# cover.net
KiCad netlist of a schematic drawn in Altium Designer
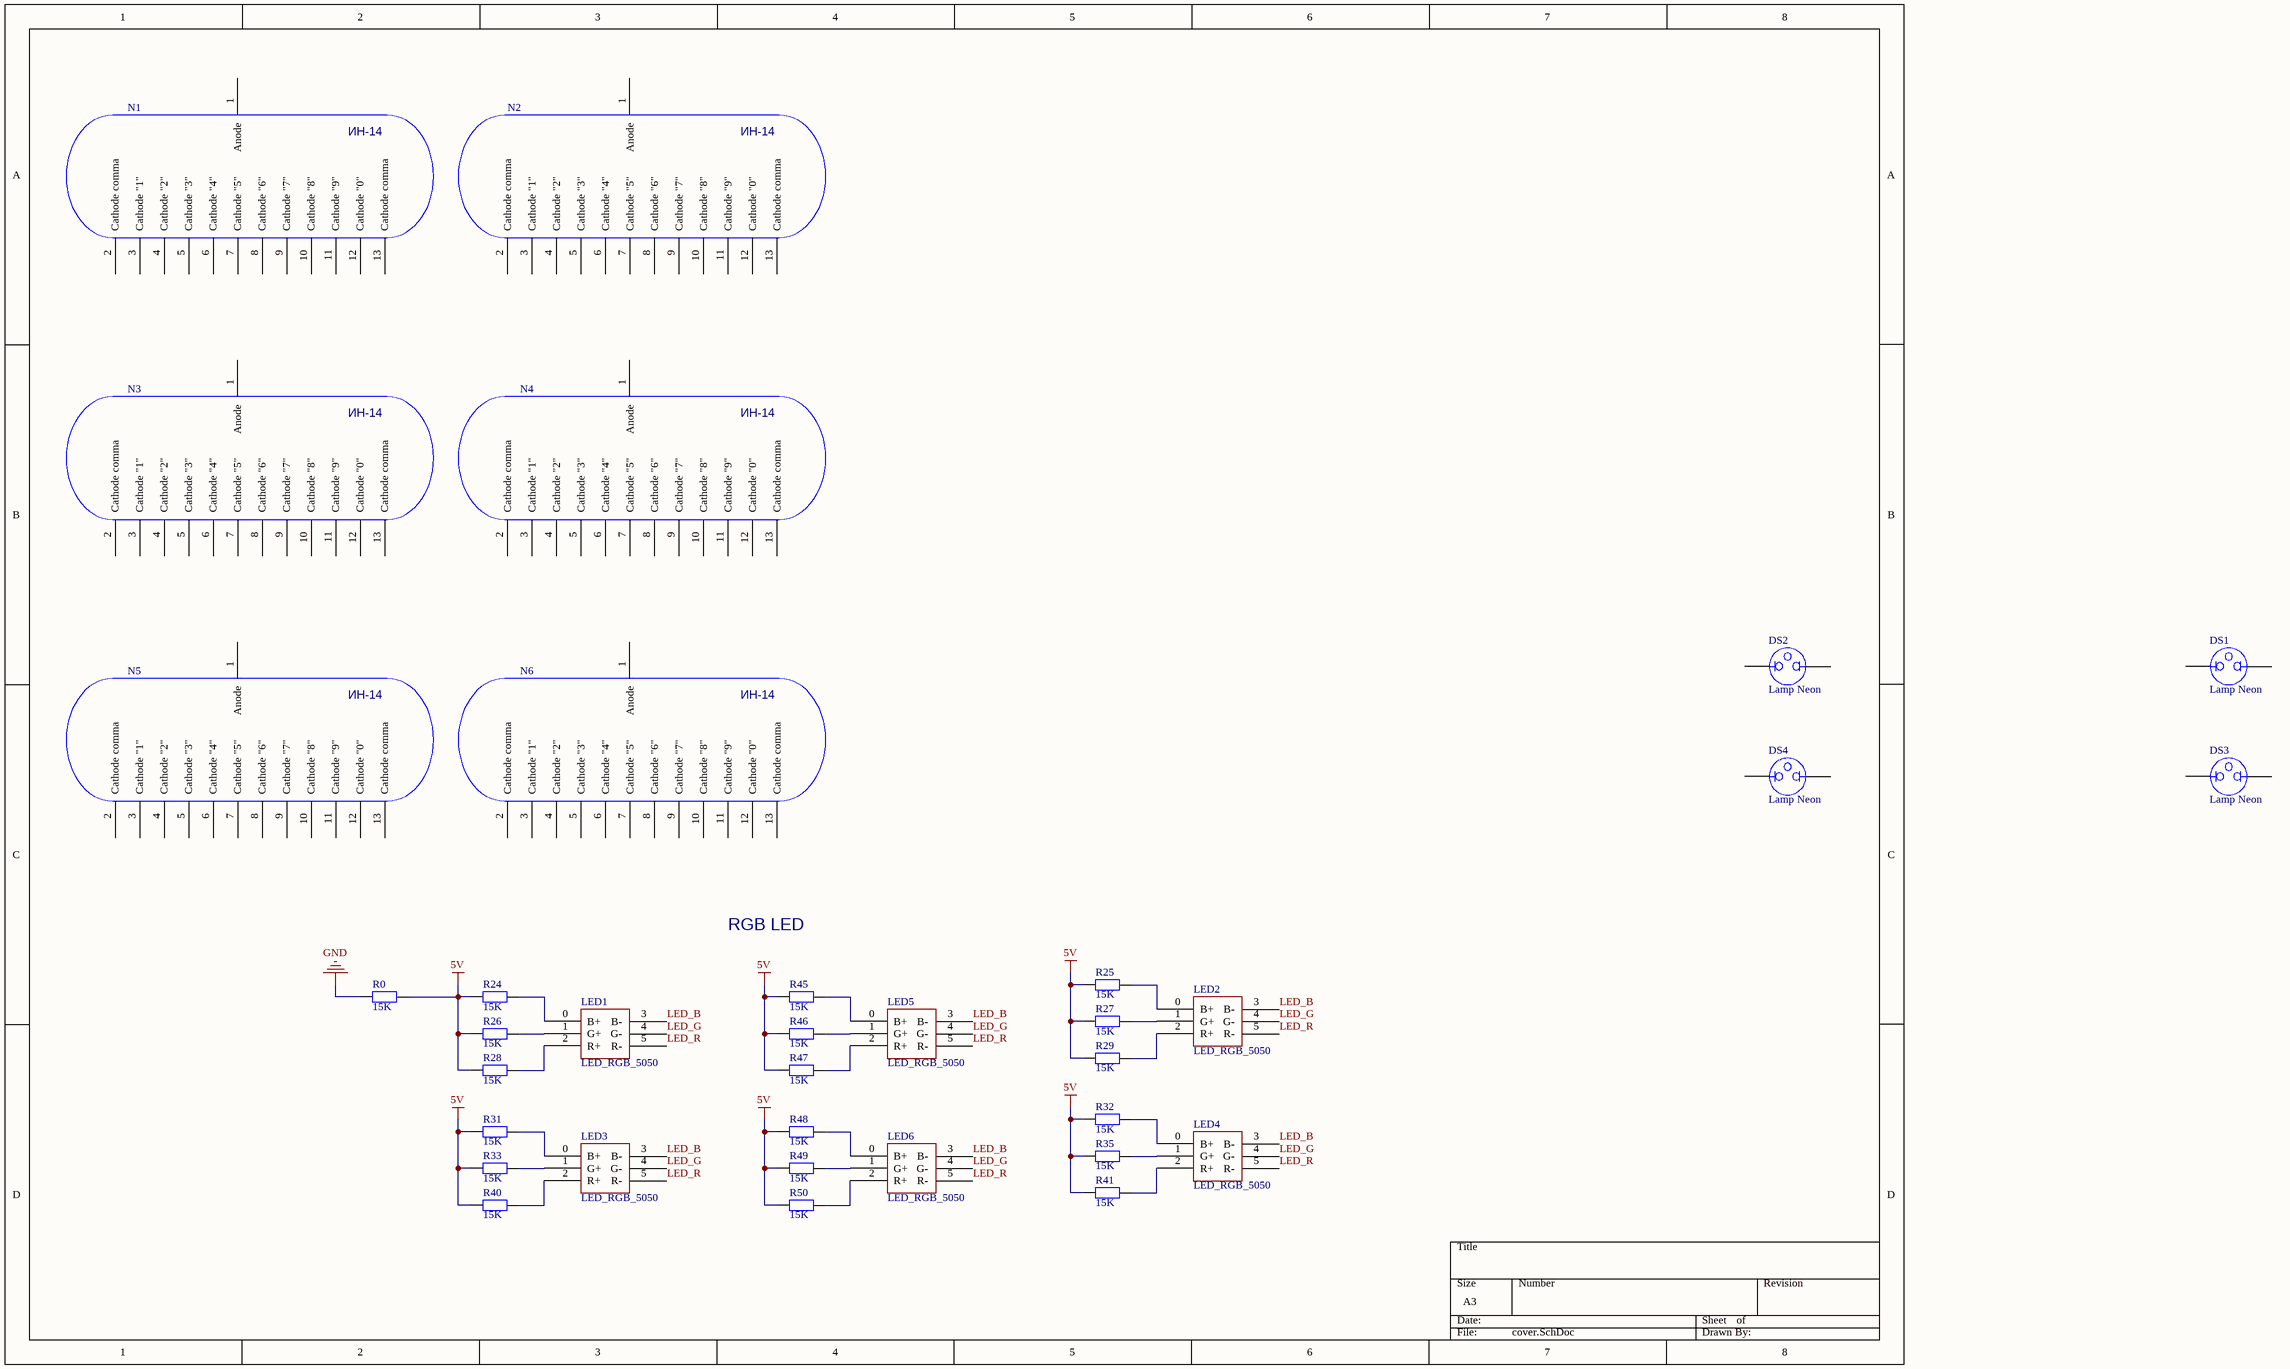
[diagram p0: cover.SchDoc]

(export (version "E")
  (design (tool "Eeschema 10.0.6"))
  (components
    (comp (ref "DS1")
      (value "Lamp Neon")
      (footprint "LED_PIN2")
      (description "Neon Lamp")
      (fields (field (name "PUBLISHER") "Altium Limited"))
      (libsource (lib "Miscellaneous Devices") (part "Lamp Neon"))
    )
    (comp (ref "DS2")
      (value "Lamp Neon")
      (footprint "LED_PIN2")
      (description "Neon Lamp")
      (fields (field (name "PUBLISHER") "Altium Limited"))
      (libsource (lib "Miscellaneous Devices") (part "Lamp Neon"))
    )
    (comp (ref "DS3")
      (value "Lamp Neon")
      (footprint "LED_PIN2")
      (description "Neon Lamp")
      (fields (field (name "PUBLISHER") "Altium Limited"))
      (libsource (lib "Miscellaneous Devices") (part "Lamp Neon"))
    )
    (comp (ref "DS4")
      (value "Lamp Neon")
      (footprint "LED_PIN2")
      (description "Neon Lamp")
      (fields (field (name "PUBLISHER") "Altium Limited"))
      (libsource (lib "Miscellaneous Devices") (part "Lamp Neon"))
    )
    (comp (ref "LED1")
      (value "LED_RGB_5050")
      (footprint "LED_RGB_5050")
      (libsource (lib "SCH") (part "LED_RGB_5050"))
    )
    (comp (ref "LED2")
      (value "LED_RGB_5050")
      (footprint "LED_RGB_5050")
      (libsource (lib "SCH") (part "LED_RGB_5050"))
    )
    (comp (ref "LED3")
      (value "LED_RGB_5050")
      (footprint "LED_RGB_5050")
      (libsource (lib "SCH") (part "LED_RGB_5050"))
    )
    (comp (ref "LED4")
      (value "LED_RGB_5050")
      (footprint "LED_RGB_5050")
      (libsource (lib "SCH") (part "LED_RGB_5050"))
    )
    (comp (ref "LED5")
      (value "LED_RGB_5050")
      (footprint "LED_RGB_5050")
      (libsource (lib "SCH") (part "LED_RGB_5050"))
    )
    (comp (ref "LED6")
      (value "LED_RGB_5050")
      (footprint "LED_RGB_5050")
      (libsource (lib "SCH") (part "LED_RGB_5050"))
    )
    (comp (ref "N1") (value "ИН-14") (footprint "IN14") (libsource (lib "NIXIEClock_SCHLib") (part "ИН-14")))
    (comp (ref "N2") (value "ИН-14") (footprint "IN14") (libsource (lib "NIXIEClock_SCHLib") (part "ИН-14")))
    (comp (ref "N3") (value "ИН-14") (footprint "IN14") (libsource (lib "NIXIEClock_SCHLib") (part "ИН-14")))
    (comp (ref "N4") (value "ИН-14") (footprint "IN14") (libsource (lib "NIXIEClock_SCHLib") (part "ИН-14")))
    (comp (ref "N5") (value "ИН-14") (footprint "IN14") (libsource (lib "NIXIEClock_SCHLib") (part "ИН-14")))
    (comp (ref "N6") (value "ИН-14") (footprint "IN14") (libsource (lib "NIXIEClock_SCHLib") (part "ИН-14")))
    (comp (ref "R0")
      (value "15K")
      (footprint "R 0603")
      (description "Resistor")
      (fields (field (name "Comment") "Res2") (field (name "PUBLISHER") "Altium Limited"))
      (libsource (lib "Miscellaneous Devices") (part "Res2"))
    )
    (comp (ref "R24")
      (value "15K")
      (footprint "R 0603")
      (description "Resistor")
      (fields (field (name "Comment") "Res2") (field (name "PUBLISHER") "Altium Limited"))
      (libsource (lib "Miscellaneous Devices") (part "Res2"))
    )
    (comp (ref "R25")
      (value "15K")
      (footprint "R 0603")
      (description "Resistor")
      (fields (field (name "Comment") "Res2") (field (name "PUBLISHER") "Altium Limited"))
      (libsource (lib "Miscellaneous Devices") (part "Res2"))
    )
    (comp (ref "R26")
      (value "15K")
      (footprint "R 0603")
      (description "Resistor")
      (fields (field (name "Comment") "Res2") (field (name "PUBLISHER") "Altium Limited"))
      (libsource (lib "Miscellaneous Devices") (part "Res2"))
    )
    (comp (ref "R27")
      (value "15K")
      (footprint "R 0603")
      (description "Resistor")
      (fields (field (name "Comment") "Res2") (field (name "PUBLISHER") "Altium Limited"))
      (libsource (lib "Miscellaneous Devices") (part "Res2"))
    )
    (comp (ref "R28")
      (value "15K")
      (footprint "R 0603")
      (description "Resistor")
      (fields (field (name "Comment") "Res2") (field (name "PUBLISHER") "Altium Limited"))
      (libsource (lib "Miscellaneous Devices") (part "Res2"))
    )
    (comp (ref "R29")
      (value "15K")
      (footprint "R 0603")
      (description "Resistor")
      (fields (field (name "Comment") "Res2") (field (name "PUBLISHER") "Altium Limited"))
      (libsource (lib "Miscellaneous Devices") (part "Res2"))
    )
    (comp (ref "R31")
      (value "15K")
      (footprint "R 0603")
      (description "Resistor")
      (fields (field (name "Comment") "Res2") (field (name "PUBLISHER") "Altium Limited"))
      (libsource (lib "Miscellaneous Devices") (part "Res2"))
    )
    (comp (ref "R32")
      (value "15K")
      (footprint "R 0603")
      (description "Resistor")
      (fields (field (name "Comment") "Res2") (field (name "PUBLISHER") "Altium Limited"))
      (libsource (lib "Miscellaneous Devices") (part "Res2"))
    )
    (comp (ref "R33")
      (value "15K")
      (footprint "R 0603")
      (description "Resistor")
      (fields (field (name "Comment") "Res2") (field (name "PUBLISHER") "Altium Limited"))
      (libsource (lib "Miscellaneous Devices") (part "Res2"))
    )
    (comp (ref "R35")
      (value "15K")
      (footprint "R 0603")
      (description "Resistor")
      (fields (field (name "Comment") "Res2") (field (name "PUBLISHER") "Altium Limited"))
      (libsource (lib "Miscellaneous Devices") (part "Res2"))
    )
    (comp (ref "R40")
      (value "15K")
      (footprint "R 0603")
      (description "Resistor")
      (fields (field (name "Comment") "Res2") (field (name "PUBLISHER") "Altium Limited"))
      (libsource (lib "Miscellaneous Devices") (part "Res2"))
    )
    (comp (ref "R41")
      (value "15K")
      (footprint "R 0603")
      (description "Resistor")
      (fields (field (name "Comment") "Res2") (field (name "PUBLISHER") "Altium Limited"))
      (libsource (lib "Miscellaneous Devices") (part "Res2"))
    )
    (comp (ref "R45")
      (value "15K")
      (footprint "R 0603")
      (description "Resistor")
      (fields (field (name "Comment") "Res2") (field (name "PUBLISHER") "Altium Limited"))
      (libsource (lib "Miscellaneous Devices") (part "Res2"))
    )
    (comp (ref "R46")
      (value "15K")
      (footprint "R 0603")
      (description "Resistor")
      (fields (field (name "Comment") "Res2") (field (name "PUBLISHER") "Altium Limited"))
      (libsource (lib "Miscellaneous Devices") (part "Res2"))
    )
    (comp (ref "R47")
      (value "15K")
      (footprint "R 0603")
      (description "Resistor")
      (fields (field (name "Comment") "Res2") (field (name "PUBLISHER") "Altium Limited"))
      (libsource (lib "Miscellaneous Devices") (part "Res2"))
    )
    (comp (ref "R48")
      (value "15K")
      (footprint "R 0603")
      (description "Resistor")
      (fields (field (name "Comment") "Res2") (field (name "PUBLISHER") "Altium Limited"))
      (libsource (lib "Miscellaneous Devices") (part "Res2"))
    )
    (comp (ref "R49")
      (value "15K")
      (footprint "R 0603")
      (description "Resistor")
      (fields (field (name "Comment") "Res2") (field (name "PUBLISHER") "Altium Limited"))
      (libsource (lib "Miscellaneous Devices") (part "Res2"))
    )
    (comp (ref "R50")
      (value "15K")
      (footprint "R 0603")
      (description "Resistor")
      (fields (field (name "Comment") "Res2") (field (name "PUBLISHER") "Altium Limited"))
      (libsource (lib "Miscellaneous Devices") (part "Res2"))
    )
  )
  (nets
    (net (code "1") (name "/LED_B") (class "Default")
      (node (ref "LED1") (pin "3") (pinfunction "B-_3") (pintype "passive"))
      (node (ref "LED2") (pin "3") (pinfunction "B-_3") (pintype "passive"))
      (node (ref "LED3") (pin "3") (pinfunction "B-_3") (pintype "passive"))
      (node (ref "LED4") (pin "3") (pinfunction "B-_3") (pintype "passive"))
      (node (ref "LED5") (pin "3") (pinfunction "B-_3") (pintype "passive"))
      (node (ref "LED6") (pin "3") (pinfunction "B-_3") (pintype "passive"))
    )
    (net (code "2") (name "/LED_G") (class "Default")
      (node (ref "LED1") (pin "4") (pinfunction "G-_4") (pintype "passive"))
      (node (ref "LED2") (pin "4") (pinfunction "G-_4") (pintype "passive"))
      (node (ref "LED3") (pin "4") (pinfunction "G-_4") (pintype "passive"))
      (node (ref "LED4") (pin "4") (pinfunction "G-_4") (pintype "passive"))
      (node (ref "LED5") (pin "4") (pinfunction "G-_4") (pintype "passive"))
      (node (ref "LED6") (pin "4") (pinfunction "G-_4") (pintype "passive"))
    )
    (net (code "3") (name "/LED_R") (class "Default")
      (node (ref "LED1") (pin "5") (pinfunction "R-_5") (pintype "passive"))
      (node (ref "LED2") (pin "5") (pinfunction "R-_5") (pintype "passive"))
      (node (ref "LED3") (pin "5") (pinfunction "R-_5") (pintype "passive"))
      (node (ref "LED4") (pin "5") (pinfunction "R-_5") (pintype "passive"))
      (node (ref "LED5") (pin "5") (pinfunction "R-_5") (pintype "passive"))
      (node (ref "LED6") (pin "5") (pinfunction "R-_5") (pintype "passive"))
    )
    (net (code "4") (name "5V") (class "Default")
      (node (ref "R0") (pin "1") (pinfunction "1_1") (pintype "passive"))
      (node (ref "R24") (pin "2") (pinfunction "2_2") (pintype "passive"))
      (node (ref "R25") (pin "2") (pinfunction "2_2") (pintype "passive"))
      (node (ref "R26") (pin "2") (pinfunction "2_2") (pintype "passive"))
      (node (ref "R27") (pin "2") (pinfunction "2_2") (pintype "passive"))
      (node (ref "R28") (pin "2") (pinfunction "2_2") (pintype "passive"))
      (node (ref "R29") (pin "2") (pinfunction "2_2") (pintype "passive"))
      (node (ref "R31") (pin "2") (pinfunction "2_2") (pintype "passive"))
      (node (ref "R32") (pin "2") (pinfunction "2_2") (pintype "passive"))
      (node (ref "R33") (pin "2") (pinfunction "2_2") (pintype "passive"))
      (node (ref "R35") (pin "2") (pinfunction "2_2") (pintype "passive"))
      (node (ref "R40") (pin "2") (pinfunction "2_2") (pintype "passive"))
      (node (ref "R41") (pin "2") (pinfunction "2_2") (pintype "passive"))
      (node (ref "R45") (pin "2") (pinfunction "2_2") (pintype "passive"))
      (node (ref "R46") (pin "2") (pinfunction "2_2") (pintype "passive"))
      (node (ref "R47") (pin "2") (pinfunction "2_2") (pintype "passive"))
      (node (ref "R48") (pin "2") (pinfunction "2_2") (pintype "passive"))
      (node (ref "R49") (pin "2") (pinfunction "2_2") (pintype "passive"))
      (node (ref "R50") (pin "2") (pinfunction "2_2") (pintype "passive"))
    )
    (net (code "5") (name "GND") (class "Default")
      (node (ref "R0") (pin "2") (pinfunction "2_2") (pintype "passive"))
    )
    (net (code "6") (name "Net-(LED1-B+)") (class "Default")
      (node (ref "LED1") (pin "0") (pinfunction "B+_0") (pintype "passive"))
      (node (ref "R24") (pin "1") (pinfunction "1_1") (pintype "passive"))
    )
    (net (code "7") (name "Net-(LED1-G+)") (class "Default")
      (node (ref "LED1") (pin "1") (pinfunction "G+_1") (pintype "passive"))
      (node (ref "R26") (pin "1") (pinfunction "1_1") (pintype "passive"))
    )
    (net (code "8") (name "Net-(LED1-R+)") (class "Default")
      (node (ref "LED1") (pin "2") (pinfunction "R+_2") (pintype "passive"))
      (node (ref "R28") (pin "1") (pinfunction "1_1") (pintype "passive"))
    )
    (net (code "9") (name "Net-(LED2-B+)") (class "Default")
      (node (ref "LED2") (pin "0") (pinfunction "B+_0") (pintype "passive"))
      (node (ref "R25") (pin "1") (pinfunction "1_1") (pintype "passive"))
    )
    (net (code "10") (name "Net-(LED2-G+)") (class "Default")
      (node (ref "LED2") (pin "1") (pinfunction "G+_1") (pintype "passive"))
      (node (ref "R27") (pin "1") (pinfunction "1_1") (pintype "passive"))
    )
    (net (code "11") (name "Net-(LED2-R+)") (class "Default")
      (node (ref "LED2") (pin "2") (pinfunction "R+_2") (pintype "passive"))
      (node (ref "R29") (pin "1") (pinfunction "1_1") (pintype "passive"))
    )
    (net (code "12") (name "Net-(LED3-B+)") (class "Default")
      (node (ref "LED3") (pin "0") (pinfunction "B+_0") (pintype "passive"))
      (node (ref "R31") (pin "1") (pinfunction "1_1") (pintype "passive"))
    )
    (net (code "13") (name "Net-(LED3-G+)") (class "Default")
      (node (ref "LED3") (pin "1") (pinfunction "G+_1") (pintype "passive"))
      (node (ref "R33") (pin "1") (pinfunction "1_1") (pintype "passive"))
    )
    (net (code "14") (name "Net-(LED3-R+)") (class "Default")
      (node (ref "LED3") (pin "2") (pinfunction "R+_2") (pintype "passive"))
      (node (ref "R40") (pin "1") (pinfunction "1_1") (pintype "passive"))
    )
    (net (code "15") (name "Net-(LED4-B+)") (class "Default")
      (node (ref "LED4") (pin "0") (pinfunction "B+_0") (pintype "passive"))
      (node (ref "R32") (pin "1") (pinfunction "1_1") (pintype "passive"))
    )
    (net (code "16") (name "Net-(LED4-G+)") (class "Default")
      (node (ref "LED4") (pin "1") (pinfunction "G+_1") (pintype "passive"))
      (node (ref "R35") (pin "1") (pinfunction "1_1") (pintype "passive"))
    )
    (net (code "17") (name "Net-(LED4-R+)") (class "Default")
      (node (ref "LED4") (pin "2") (pinfunction "R+_2") (pintype "passive"))
      (node (ref "R41") (pin "1") (pinfunction "1_1") (pintype "passive"))
    )
    (net (code "18") (name "Net-(LED5-B+)") (class "Default")
      (node (ref "LED5") (pin "0") (pinfunction "B+_0") (pintype "passive"))
      (node (ref "R45") (pin "1") (pinfunction "1_1") (pintype "passive"))
    )
    (net (code "19") (name "Net-(LED5-G+)") (class "Default")
      (node (ref "LED5") (pin "1") (pinfunction "G+_1") (pintype "passive"))
      (node (ref "R46") (pin "1") (pinfunction "1_1") (pintype "passive"))
    )
    (net (code "20") (name "Net-(LED5-R+)") (class "Default")
      (node (ref "LED5") (pin "2") (pinfunction "R+_2") (pintype "passive"))
      (node (ref "R47") (pin "1") (pinfunction "1_1") (pintype "passive"))
    )
    (net (code "21") (name "Net-(LED6-B+)") (class "Default")
      (node (ref "LED6") (pin "0") (pinfunction "B+_0") (pintype "passive"))
      (node (ref "R48") (pin "1") (pinfunction "1_1") (pintype "passive"))
    )
    (net (code "22") (name "Net-(LED6-G+)") (class "Default")
      (node (ref "LED6") (pin "1") (pinfunction "G+_1") (pintype "passive"))
      (node (ref "R49") (pin "1") (pinfunction "1_1") (pintype "passive"))
    )
    (net (code "23") (name "Net-(LED6-R+)") (class "Default")
      (node (ref "LED6") (pin "2") (pinfunction "R+_2") (pintype "passive"))
      (node (ref "R50") (pin "1") (pinfunction "1_1") (pintype "passive"))
    )
    (net (code "24") (name "unconnected-(DS1-Pad1)") (class "Default")
      (node (ref "DS1") (pin "1") (pinfunction "1_1") (pintype "passive"))
    )
    (net (code "25") (name "unconnected-(DS1-Pad2)") (class "Default")
      (node (ref "DS1") (pin "2") (pinfunction "2_2") (pintype "passive"))
    )
    (net (code "26") (name "unconnected-(DS2-Pad1)") (class "Default")
      (node (ref "DS2") (pin "1") (pinfunction "1_1") (pintype "passive"))
    )
    (net (code "27") (name "unconnected-(DS2-Pad2)") (class "Default")
      (node (ref "DS2") (pin "2") (pinfunction "2_2") (pintype "passive"))
    )
    (net (code "28") (name "unconnected-(DS3-Pad1)") (class "Default")
      (node (ref "DS3") (pin "1") (pinfunction "1_1") (pintype "passive"))
    )
    (net (code "29") (name "unconnected-(DS3-Pad2)") (class "Default")
      (node (ref "DS3") (pin "2") (pinfunction "2_2") (pintype "passive"))
    )
    (net (code "30") (name "unconnected-(DS4-Pad1)") (class "Default")
      (node (ref "DS4") (pin "1") (pinfunction "1_1") (pintype "passive"))
    )
    (net (code "31") (name "unconnected-(DS4-Pad2)") (class "Default")
      (node (ref "DS4") (pin "2") (pinfunction "2_2") (pintype "passive"))
    )
    (net (code "32") (name "unconnected-(N1-Anode-Pad1)") (class "Default")
      (node (ref "N1") (pin "1") (pinfunction "Anode_1") (pintype "passive"))
    )
    (net (code "33") (name "unconnected-(N1-Cathode_\"0\"-Pad12)") (class "Default")
      (node (ref "N1") (pin "12") (pinfunction "Cathode_\"0\"_12") (pintype "passive"))
    )
    (net (code "34") (name "unconnected-(N1-Cathode_\"1\"-Pad3)") (class "Default")
      (node (ref "N1") (pin "3") (pinfunction "Cathode_\"1\"_3") (pintype "passive"))
    )
    (net (code "35") (name "unconnected-(N1-Cathode_\"2\"-Pad4)") (class "Default")
      (node (ref "N1") (pin "4") (pinfunction "Cathode_\"2\"_4") (pintype "passive"))
    )
    (net (code "36") (name "unconnected-(N1-Cathode_\"3\"-Pad5)") (class "Default")
      (node (ref "N1") (pin "5") (pinfunction "Cathode_\"3\"_5") (pintype "passive"))
    )
    (net (code "37") (name "unconnected-(N1-Cathode_\"4\"-Pad6)") (class "Default")
      (node (ref "N1") (pin "6") (pinfunction "Cathode_\"4\"_6") (pintype "passive"))
    )
    (net (code "38") (name "unconnected-(N1-Cathode_\"5\"-Pad7)") (class "Default")
      (node (ref "N1") (pin "7") (pinfunction "Cathode_\"5\"_7") (pintype "passive"))
    )
    (net (code "39") (name "unconnected-(N1-Cathode_\"6\"-Pad8)") (class "Default")
      (node (ref "N1") (pin "8") (pinfunction "Cathode_\"6\"_8") (pintype "passive"))
    )
    (net (code "40") (name "unconnected-(N1-Cathode_\"7\"-Pad9)") (class "Default")
      (node (ref "N1") (pin "9") (pinfunction "Cathode_\"7\"_9") (pintype "passive"))
    )
    (net (code "41") (name "unconnected-(N1-Cathode_\"8\"-Pad10)") (class "Default")
      (node (ref "N1") (pin "10") (pinfunction "Cathode_\"8\"_10") (pintype "passive"))
    )
    (net (code "42") (name "unconnected-(N1-Cathode_\"9\"-Pad11)") (class "Default")
      (node (ref "N1") (pin "11") (pinfunction "Cathode_\"9\"_11") (pintype "passive"))
    )
    (net (code "43") (name "unconnected-(N1-Cathode_comma-Pad2)") (class "Default")
      (node (ref "N1") (pin "2") (pinfunction "Cathode_comma_2") (pintype "passive"))
    )
    (net (code "44") (name "unconnected-(N1-Cathode_comma-Pad13)") (class "Default")
      (node (ref "N1") (pin "13") (pinfunction "Cathode_comma_13") (pintype "passive"))
    )
    (net (code "45") (name "unconnected-(N2-Anode-Pad1)") (class "Default")
      (node (ref "N2") (pin "1") (pinfunction "Anode_1") (pintype "passive"))
    )
    (net (code "46") (name "unconnected-(N2-Cathode_\"0\"-Pad12)") (class "Default")
      (node (ref "N2") (pin "12") (pinfunction "Cathode_\"0\"_12") (pintype "passive"))
    )
    (net (code "47") (name "unconnected-(N2-Cathode_\"1\"-Pad3)") (class "Default")
      (node (ref "N2") (pin "3") (pinfunction "Cathode_\"1\"_3") (pintype "passive"))
    )
    (net (code "48") (name "unconnected-(N2-Cathode_\"2\"-Pad4)") (class "Default")
      (node (ref "N2") (pin "4") (pinfunction "Cathode_\"2\"_4") (pintype "passive"))
    )
    (net (code "49") (name "unconnected-(N2-Cathode_\"3\"-Pad5)") (class "Default")
      (node (ref "N2") (pin "5") (pinfunction "Cathode_\"3\"_5") (pintype "passive"))
    )
    (net (code "50") (name "unconnected-(N2-Cathode_\"4\"-Pad6)") (class "Default")
      (node (ref "N2") (pin "6") (pinfunction "Cathode_\"4\"_6") (pintype "passive"))
    )
    (net (code "51") (name "unconnected-(N2-Cathode_\"5\"-Pad7)") (class "Default")
      (node (ref "N2") (pin "7") (pinfunction "Cathode_\"5\"_7") (pintype "passive"))
    )
    (net (code "52") (name "unconnected-(N2-Cathode_\"6\"-Pad8)") (class "Default")
      (node (ref "N2") (pin "8") (pinfunction "Cathode_\"6\"_8") (pintype "passive"))
    )
    (net (code "53") (name "unconnected-(N2-Cathode_\"7\"-Pad9)") (class "Default")
      (node (ref "N2") (pin "9") (pinfunction "Cathode_\"7\"_9") (pintype "passive"))
    )
    (net (code "54") (name "unconnected-(N2-Cathode_\"8\"-Pad10)") (class "Default")
      (node (ref "N2") (pin "10") (pinfunction "Cathode_\"8\"_10") (pintype "passive"))
    )
    (net (code "55") (name "unconnected-(N2-Cathode_\"9\"-Pad11)") (class "Default")
      (node (ref "N2") (pin "11") (pinfunction "Cathode_\"9\"_11") (pintype "passive"))
    )
    (net (code "56") (name "unconnected-(N2-Cathode_comma-Pad2)") (class "Default")
      (node (ref "N2") (pin "2") (pinfunction "Cathode_comma_2") (pintype "passive"))
    )
    (net (code "57") (name "unconnected-(N2-Cathode_comma-Pad13)") (class "Default")
      (node (ref "N2") (pin "13") (pinfunction "Cathode_comma_13") (pintype "passive"))
    )
    (net (code "58") (name "unconnected-(N3-Anode-Pad1)") (class "Default")
      (node (ref "N3") (pin "1") (pinfunction "Anode_1") (pintype "passive"))
    )
    (net (code "59") (name "unconnected-(N3-Cathode_\"0\"-Pad12)") (class "Default")
      (node (ref "N3") (pin "12") (pinfunction "Cathode_\"0\"_12") (pintype "passive"))
    )
    (net (code "60") (name "unconnected-(N3-Cathode_\"1\"-Pad3)") (class "Default")
      (node (ref "N3") (pin "3") (pinfunction "Cathode_\"1\"_3") (pintype "passive"))
    )
    (net (code "61") (name "unconnected-(N3-Cathode_\"2\"-Pad4)") (class "Default")
      (node (ref "N3") (pin "4") (pinfunction "Cathode_\"2\"_4") (pintype "passive"))
    )
    (net (code "62") (name "unconnected-(N3-Cathode_\"3\"-Pad5)") (class "Default")
      (node (ref "N3") (pin "5") (pinfunction "Cathode_\"3\"_5") (pintype "passive"))
    )
    (net (code "63") (name "unconnected-(N3-Cathode_\"4\"-Pad6)") (class "Default")
      (node (ref "N3") (pin "6") (pinfunction "Cathode_\"4\"_6") (pintype "passive"))
    )
    (net (code "64") (name "unconnected-(N3-Cathode_\"5\"-Pad7)") (class "Default")
      (node (ref "N3") (pin "7") (pinfunction "Cathode_\"5\"_7") (pintype "passive"))
    )
    (net (code "65") (name "unconnected-(N3-Cathode_\"6\"-Pad8)") (class "Default")
      (node (ref "N3") (pin "8") (pinfunction "Cathode_\"6\"_8") (pintype "passive"))
    )
    (net (code "66") (name "unconnected-(N3-Cathode_\"7\"-Pad9)") (class "Default")
      (node (ref "N3") (pin "9") (pinfunction "Cathode_\"7\"_9") (pintype "passive"))
    )
    (net (code "67") (name "unconnected-(N3-Cathode_\"8\"-Pad10)") (class "Default")
      (node (ref "N3") (pin "10") (pinfunction "Cathode_\"8\"_10") (pintype "passive"))
    )
    (net (code "68") (name "unconnected-(N3-Cathode_\"9\"-Pad11)") (class "Default")
      (node (ref "N3") (pin "11") (pinfunction "Cathode_\"9\"_11") (pintype "passive"))
    )
    (net (code "69") (name "unconnected-(N3-Cathode_comma-Pad2)") (class "Default")
      (node (ref "N3") (pin "2") (pinfunction "Cathode_comma_2") (pintype "passive"))
    )
    (net (code "70") (name "unconnected-(N3-Cathode_comma-Pad13)") (class "Default")
      (node (ref "N3") (pin "13") (pinfunction "Cathode_comma_13") (pintype "passive"))
    )
    (net (code "71") (name "unconnected-(N4-Anode-Pad1)") (class "Default")
      (node (ref "N4") (pin "1") (pinfunction "Anode_1") (pintype "passive"))
    )
    (net (code "72") (name "unconnected-(N4-Cathode_\"0\"-Pad12)") (class "Default")
      (node (ref "N4") (pin "12") (pinfunction "Cathode_\"0\"_12") (pintype "passive"))
    )
    (net (code "73") (name "unconnected-(N4-Cathode_\"1\"-Pad3)") (class "Default")
      (node (ref "N4") (pin "3") (pinfunction "Cathode_\"1\"_3") (pintype "passive"))
    )
    (net (code "74") (name "unconnected-(N4-Cathode_\"2\"-Pad4)") (class "Default")
      (node (ref "N4") (pin "4") (pinfunction "Cathode_\"2\"_4") (pintype "passive"))
    )
    (net (code "75") (name "unconnected-(N4-Cathode_\"3\"-Pad5)") (class "Default")
      (node (ref "N4") (pin "5") (pinfunction "Cathode_\"3\"_5") (pintype "passive"))
    )
    (net (code "76") (name "unconnected-(N4-Cathode_\"4\"-Pad6)") (class "Default")
      (node (ref "N4") (pin "6") (pinfunction "Cathode_\"4\"_6") (pintype "passive"))
    )
    (net (code "77") (name "unconnected-(N4-Cathode_\"5\"-Pad7)") (class "Default")
      (node (ref "N4") (pin "7") (pinfunction "Cathode_\"5\"_7") (pintype "passive"))
    )
    (net (code "78") (name "unconnected-(N4-Cathode_\"6\"-Pad8)") (class "Default")
      (node (ref "N4") (pin "8") (pinfunction "Cathode_\"6\"_8") (pintype "passive"))
    )
    (net (code "79") (name "unconnected-(N4-Cathode_\"7\"-Pad9)") (class "Default")
      (node (ref "N4") (pin "9") (pinfunction "Cathode_\"7\"_9") (pintype "passive"))
    )
    (net (code "80") (name "unconnected-(N4-Cathode_\"8\"-Pad10)") (class "Default")
      (node (ref "N4") (pin "10") (pinfunction "Cathode_\"8\"_10") (pintype "passive"))
    )
    (net (code "81") (name "unconnected-(N4-Cathode_\"9\"-Pad11)") (class "Default")
      (node (ref "N4") (pin "11") (pinfunction "Cathode_\"9\"_11") (pintype "passive"))
    )
    (net (code "82") (name "unconnected-(N4-Cathode_comma-Pad2)") (class "Default")
      (node (ref "N4") (pin "2") (pinfunction "Cathode_comma_2") (pintype "passive"))
    )
    (net (code "83") (name "unconnected-(N4-Cathode_comma-Pad13)") (class "Default")
      (node (ref "N4") (pin "13") (pinfunction "Cathode_comma_13") (pintype "passive"))
    )
    (net (code "84") (name "unconnected-(N5-Anode-Pad1)") (class "Default")
      (node (ref "N5") (pin "1") (pinfunction "Anode_1") (pintype "passive"))
    )
    (net (code "85") (name "unconnected-(N5-Cathode_\"0\"-Pad12)") (class "Default")
      (node (ref "N5") (pin "12") (pinfunction "Cathode_\"0\"_12") (pintype "passive"))
    )
    (net (code "86") (name "unconnected-(N5-Cathode_\"1\"-Pad3)") (class "Default")
      (node (ref "N5") (pin "3") (pinfunction "Cathode_\"1\"_3") (pintype "passive"))
    )
    (net (code "87") (name "unconnected-(N5-Cathode_\"2\"-Pad4)") (class "Default")
      (node (ref "N5") (pin "4") (pinfunction "Cathode_\"2\"_4") (pintype "passive"))
    )
    (net (code "88") (name "unconnected-(N5-Cathode_\"3\"-Pad5)") (class "Default")
      (node (ref "N5") (pin "5") (pinfunction "Cathode_\"3\"_5") (pintype "passive"))
    )
    (net (code "89") (name "unconnected-(N5-Cathode_\"4\"-Pad6)") (class "Default")
      (node (ref "N5") (pin "6") (pinfunction "Cathode_\"4\"_6") (pintype "passive"))
    )
    (net (code "90") (name "unconnected-(N5-Cathode_\"5\"-Pad7)") (class "Default")
      (node (ref "N5") (pin "7") (pinfunction "Cathode_\"5\"_7") (pintype "passive"))
    )
    (net (code "91") (name "unconnected-(N5-Cathode_\"6\"-Pad8)") (class "Default")
      (node (ref "N5") (pin "8") (pinfunction "Cathode_\"6\"_8") (pintype "passive"))
    )
    (net (code "92") (name "unconnected-(N5-Cathode_\"7\"-Pad9)") (class "Default")
      (node (ref "N5") (pin "9") (pinfunction "Cathode_\"7\"_9") (pintype "passive"))
    )
    (net (code "93") (name "unconnected-(N5-Cathode_\"8\"-Pad10)") (class "Default")
      (node (ref "N5") (pin "10") (pinfunction "Cathode_\"8\"_10") (pintype "passive"))
    )
    (net (code "94") (name "unconnected-(N5-Cathode_\"9\"-Pad11)") (class "Default")
      (node (ref "N5") (pin "11") (pinfunction "Cathode_\"9\"_11") (pintype "passive"))
    )
    (net (code "95") (name "unconnected-(N5-Cathode_comma-Pad2)") (class "Default")
      (node (ref "N5") (pin "2") (pinfunction "Cathode_comma_2") (pintype "passive"))
    )
    (net (code "96") (name "unconnected-(N5-Cathode_comma-Pad13)") (class "Default")
      (node (ref "N5") (pin "13") (pinfunction "Cathode_comma_13") (pintype "passive"))
    )
    (net (code "97") (name "unconnected-(N6-Anode-Pad1)") (class "Default")
      (node (ref "N6") (pin "1") (pinfunction "Anode_1") (pintype "passive"))
    )
    (net (code "98") (name "unconnected-(N6-Cathode_\"0\"-Pad12)") (class "Default")
      (node (ref "N6") (pin "12") (pinfunction "Cathode_\"0\"_12") (pintype "passive"))
    )
    (net (code "99") (name "unconnected-(N6-Cathode_\"1\"-Pad3)") (class "Default")
      (node (ref "N6") (pin "3") (pinfunction "Cathode_\"1\"_3") (pintype "passive"))
    )
    (net (code "100") (name "unconnected-(N6-Cathode_\"2\"-Pad4)") (class "Default")
      (node (ref "N6") (pin "4") (pinfunction "Cathode_\"2\"_4") (pintype "passive"))
    )
    (net (code "101") (name "unconnected-(N6-Cathode_\"3\"-Pad5)") (class "Default")
      (node (ref "N6") (pin "5") (pinfunction "Cathode_\"3\"_5") (pintype "passive"))
    )
    (net (code "102") (name "unconnected-(N6-Cathode_\"4\"-Pad6)") (class "Default")
      (node (ref "N6") (pin "6") (pinfunction "Cathode_\"4\"_6") (pintype "passive"))
    )
    (net (code "103") (name "unconnected-(N6-Cathode_\"5\"-Pad7)") (class "Default")
      (node (ref "N6") (pin "7") (pinfunction "Cathode_\"5\"_7") (pintype "passive"))
    )
    (net (code "104") (name "unconnected-(N6-Cathode_\"6\"-Pad8)") (class "Default")
      (node (ref "N6") (pin "8") (pinfunction "Cathode_\"6\"_8") (pintype "passive"))
    )
    (net (code "105") (name "unconnected-(N6-Cathode_\"7\"-Pad9)") (class "Default")
      (node (ref "N6") (pin "9") (pinfunction "Cathode_\"7\"_9") (pintype "passive"))
    )
    (net (code "106") (name "unconnected-(N6-Cathode_\"8\"-Pad10)") (class "Default")
      (node (ref "N6") (pin "10") (pinfunction "Cathode_\"8\"_10") (pintype "passive"))
    )
    (net (code "107") (name "unconnected-(N6-Cathode_\"9\"-Pad11)") (class "Default")
      (node (ref "N6") (pin "11") (pinfunction "Cathode_\"9\"_11") (pintype "passive"))
    )
    (net (code "108") (name "unconnected-(N6-Cathode_comma-Pad2)") (class "Default")
      (node (ref "N6") (pin "2") (pinfunction "Cathode_comma_2") (pintype "passive"))
    )
    (net (code "109") (name "unconnected-(N6-Cathode_comma-Pad13)") (class "Default")
      (node (ref "N6") (pin "13") (pinfunction "Cathode_comma_13") (pintype "passive"))
    )
  )
)
